# Sheet1.net
KiCad netlist of a schematic drawn in Altium Designer
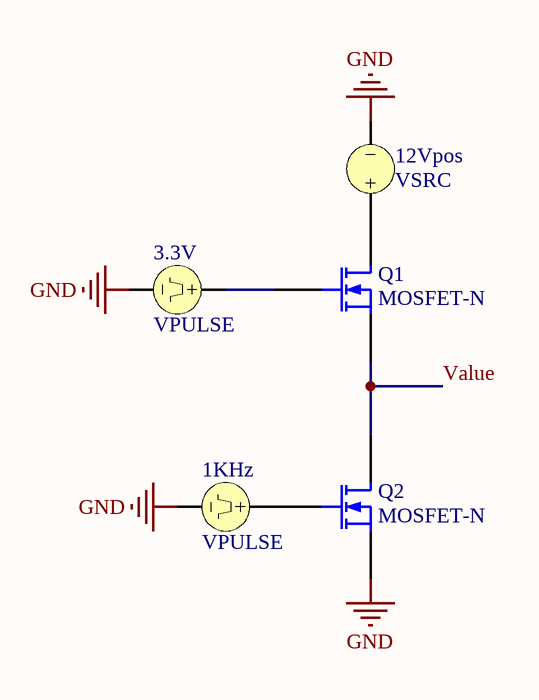
[diagram p0: Sheet1.SchDoc]

(export (version "E")
  (design (tool "Eeschema 10.0.6"))
  (components
    (comp (ref "1KHz")
      (value "VPULSE")
      (description "Pulse Voltage Source")
      (fields (field (name "PUBLISHER") "Altium Limited"))
      (libsource (lib "Simulation Sources") (part "VPULSE"))
    )
    (comp (ref "3.3V")
      (value "VPULSE")
      (description "Pulse Voltage Source")
      (fields (field (name "PUBLISHER") "Altium Limited"))
      (libsource (lib "Simulation Sources") (part "VPULSE"))
    )
    (comp (ref "12Vpos")
      (value "VSRC")
      (description "Voltage Source")
      (fields (field (name "PUBLISHER") "Altium Limited"))
      (libsource (lib "Simulation Sources") (part "VSRC"))
    )
    (comp (ref "Q1")
      (value "MOSFET-N")
      (footprint "E3")
      (description "N-Channel MOSFET")
      (fields (field (name "PUBLISHER") "Altium Limited"))
      (libsource (lib "Miscellaneous Devices") (part "MOSFET-N"))
    )
    (comp (ref "Q2")
      (value "MOSFET-N")
      (footprint "E3")
      (description "N-Channel MOSFET")
      (fields (field (name "PUBLISHER") "Altium Limited"))
      (libsource (lib "Miscellaneous Devices") (part "MOSFET-N"))
    )
  )
  (nets
    (net (code "1") (name "/Value") (class "Default")
      (node (ref "Q1") (pin "3") (pinfunction "S_3") (pintype "passive"))
      (node (ref "Q2") (pin "1") (pinfunction "D_1") (pintype "passive"))
    )
    (net (code "2") (name "GND") (class "Default")
      (node (ref "12Vpos") (pin "2") (pinfunction "2_2") (pintype "passive"))
      (node (ref "1KHz") (pin "2") (pinfunction "2_2") (pintype "passive"))
      (node (ref "3.3V") (pin "2") (pinfunction "2_2") (pintype "passive"))
      (node (ref "Q2") (pin "3") (pinfunction "S_3") (pintype "passive"))
    )
    (net (code "3") (name "Net-(Q1-D)") (class "Default")
      (node (ref "12Vpos") (pin "1") (pinfunction "1_1") (pintype "passive"))
      (node (ref "Q1") (pin "1") (pinfunction "D_1") (pintype "passive"))
    )
    (net (code "4") (name "Net-(Q1-G)") (class "Default")
      (node (ref "3.3V") (pin "1") (pinfunction "1_1") (pintype "passive"))
      (node (ref "Q1") (pin "2") (pinfunction "G_2") (pintype "passive"))
    )
    (net (code "5") (name "Net-(Q2-G)") (class "Default")
      (node (ref "1KHz") (pin "1") (pinfunction "1_1") (pintype "passive"))
      (node (ref "Q2") (pin "2") (pinfunction "G_2") (pintype "passive"))
    )
  )
)
